# E17-04_DC_DC_CONTROL.net
KiCad netlist of a schematic drawn in Altium Designer
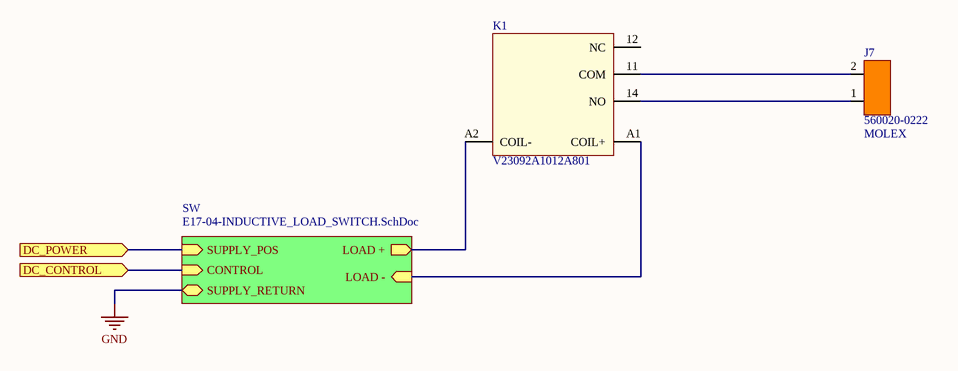
[diagram p0: E17-04_DC_DC_CONTROL.SchDoc]

(export (version "E")
  (design (tool "Eeschema 10.0.6"))
  (components
    (comp (ref "J7")
      (value "DC TO DC")
      (footprint "MOLEX_DURACLIK_2 RED VERT")
      (description "MOLEX DURACLIK 2-PIN VERT RED")
      (fields
        (field (name "VOLTAGE") "125")
        (field (name "MPN") "560020-0222")
        (field (name "MANUFACTURER") "MOLEX")
      )
      (libsource (lib "Molex_DuraClik") (part "560020-0222"))
    )
    (comp (ref "K1")
      (value "V23092A1012A801")
      (footprint "SCHRACK")
      (description "12V slim SPDT Relay")
      (fields (field (name "MFG") "TE") (field (name "MFG_PN") "V23092A1012A801"))
      (libsource (lib "Relays") (part "V23092A1012A801"))
    )
  )
  (nets
    (net (code "3") (name "/LOAD +") (class "Default")
      (node (ref "K1") (pin "A2") (pinfunction "COIL-_A2") (pintype "passive"))
    )
    (net (code "4") (name "/LOAD -") (class "Default")
      (node (ref "K1") (pin "A1") (pinfunction "COIL+_A1") (pintype "passive"))
    )
    (net (code "6") (name "Net-(K1-COM)") (class "Default")
      (node (ref "J7") (pin "2") (pinfunction "2_2") (pintype "passive"))
      (node (ref "K1") (pin "11") (pinfunction "COM_11") (pintype "passive"))
    )
    (net (code "7") (name "Net-(K1-NO)") (class "Default")
      (node (ref "J7") (pin "1") (pinfunction "1_1") (pintype "passive"))
      (node (ref "K1") (pin "14") (pinfunction "NO_14") (pintype "passive"))
    )
    (net (code "8") (name "unconnected-(K1-NC-Pad12)") (class "Default")
      (node (ref "K1") (pin "12") (pinfunction "NC_12") (pintype "passive"))
    )
  )
)
